# Top_Level.net
KiCad netlist of a schematic drawn in Altium Designer
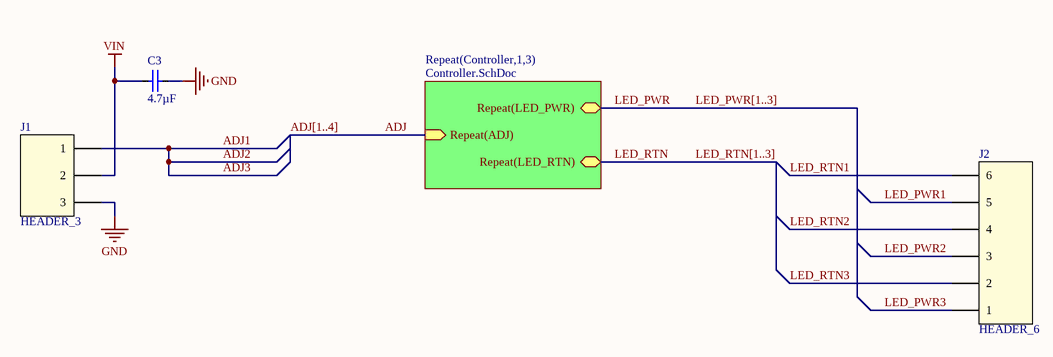
[diagram p0: Top Level.SchDoc]

(export (version "E")
  (design (tool "Eeschema 10.0.6"))
  (components
    (comp (ref "C3")
      (value "4.7µF")
      (footprint "CAP_1206")
      (description "Capacitor")
      (fields
        (field (name "MANUFACTURER") "TDK Corporation")
        (field (name "MANUFACTURER PART NUMBER") "C3216X7R1V475M160AE")
      )
      (libsource (lib "RUssery") (part "CAPACITOR"))
    )
    (comp (ref "J1")
      (value "HEADER_3")
      (footprint "MOLEX_C-GRID3_3PIN")
      (libsource (lib "RUssery") (part "HEADER_3"))
    )
    (comp (ref "J2")
      (value "HEADER_6")
      (footprint "MOLEX_C-GRID3_6PIN")
      (libsource (lib "RUssery") (part "HEADER_6"))
    )
  )
  (nets
    (net (code "3") (name "/ADJ3") (class "Default")
      (node (ref "J1") (pin "1") (pinfunction "1_1") (pintype "passive"))
    )
    (net (code "6") (name "/LED_PWR1") (class "Default")
      (node (ref "J2") (pin "5") (pinfunction "5_5") (pintype "passive"))
    )
    (net (code "7") (name "/LED_PWR2") (class "Default")
      (node (ref "J2") (pin "3") (pinfunction "3_3") (pintype "passive"))
    )
    (net (code "8") (name "/LED_PWR3") (class "Default")
      (node (ref "J2") (pin "1") (pinfunction "1_1") (pintype "passive"))
    )
    (net (code "11") (name "/LED_RTN1") (class "Default")
      (node (ref "J2") (pin "6") (pinfunction "6_6") (pintype "passive"))
    )
    (net (code "12") (name "/LED_RTN2") (class "Default")
      (node (ref "J2") (pin "4") (pinfunction "4_4") (pintype "passive"))
    )
    (net (code "13") (name "/LED_RTN3") (class "Default")
      (node (ref "J2") (pin "2") (pinfunction "2_2") (pintype "passive"))
    )
    (net (code "15") (name "GND") (class "Default")
      (node (ref "C3") (pin "2") (pinfunction "2_2") (pintype "passive"))
      (node (ref "J1") (pin "3") (pinfunction "3_3") (pintype "passive"))
    )
    (net (code "16") (name "VIN") (class "Default")
      (node (ref "C3") (pin "1") (pinfunction "1_1") (pintype "passive"))
      (node (ref "J1") (pin "2") (pinfunction "2_2") (pintype "passive"))
    )
  )
)
